# PAGE05_88-QFN-DEVICE_CO.net
KiCad netlist of a schematic drawn in Altium Designer
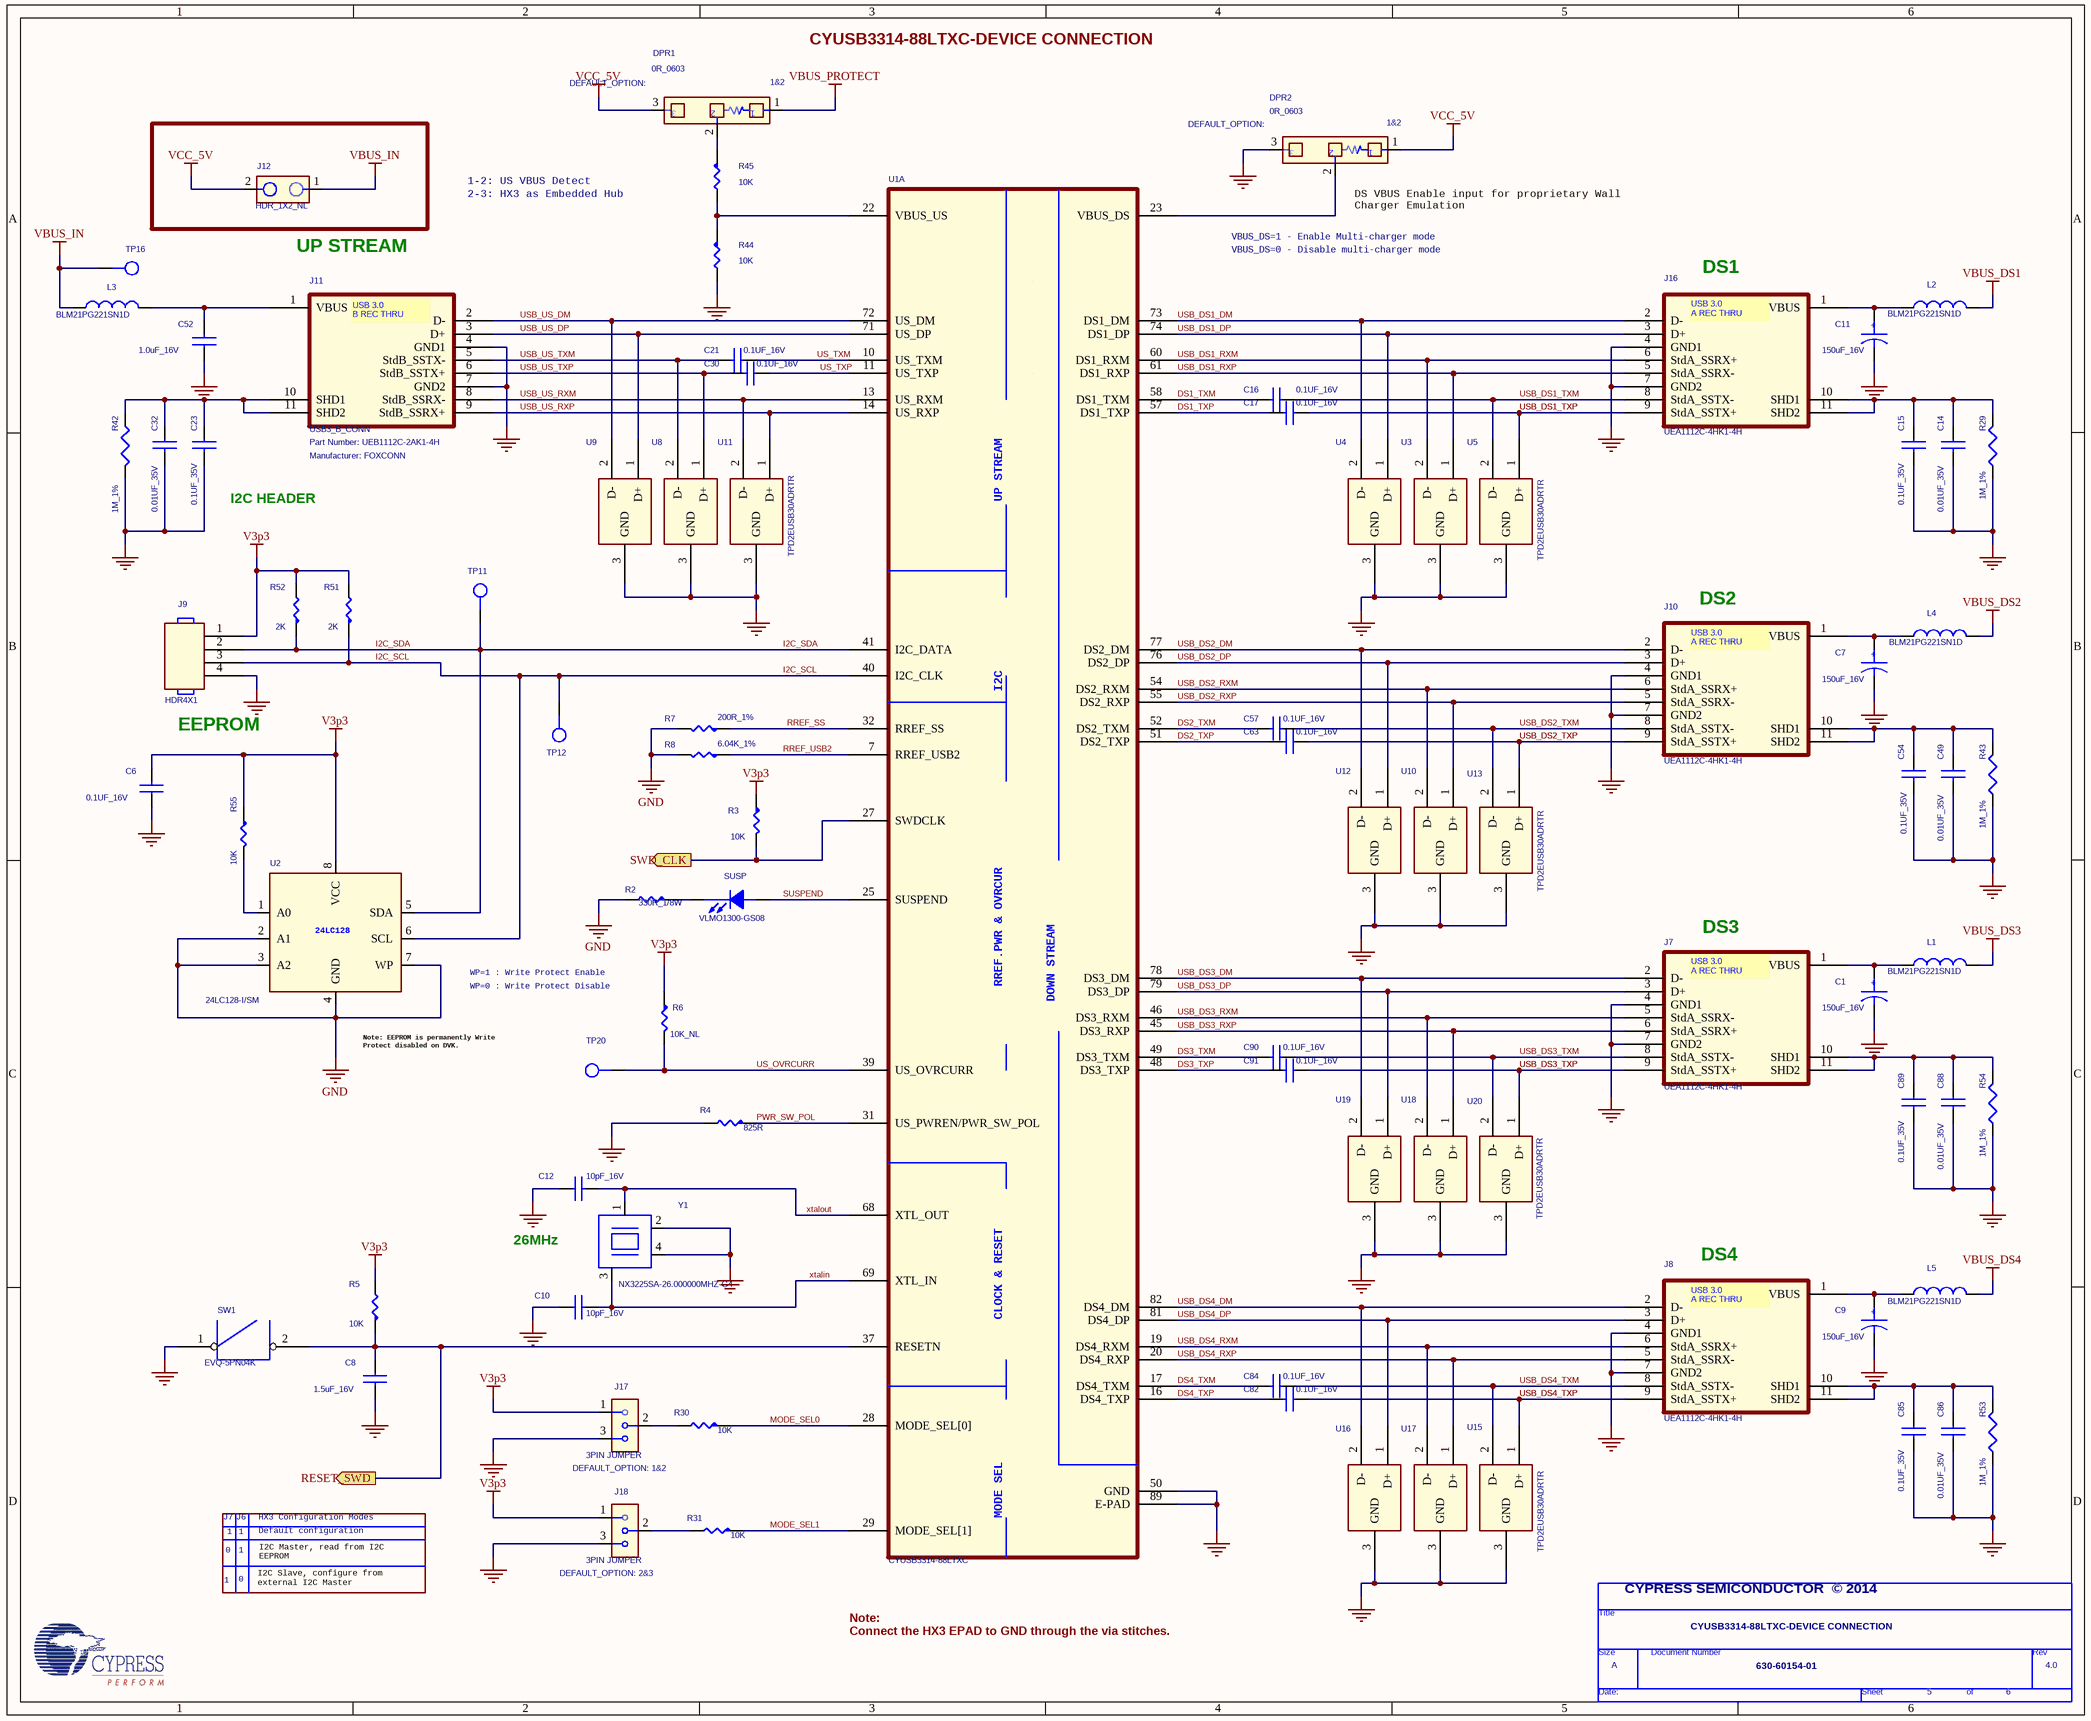
[diagram p0: PAGE05_88-QFN-DEVICE CO.SchDoc]

(export (version "E")
  (design (tool "Eeschema 10.0.6"))
  (components
    (comp (ref "*")
      (value "TitleBlock0")
      (fields
        (field (name "PAGE COUNT") "6")
        (field (name "PAGE NUMBER") "5")
        (field (name "PAGE SIZE") "A")
        (field (name "TITLE") "CYUSB3314-88LTXC-DEVICE CONNECTION")
        (field (name "REVCODE") "4.0")
        (field (name "DOC") "630-60154-01")
      )
      (libsource (lib "*") (part "TitleBlock0"))
    )
    (comp (ref "C1")
      (value "150uF_16V")
      (description "CAP ALUM 150UF 16V 20% SMD")
      (fields
        (field (name "PART NUMBER") "EEE-FK1C151XP")
        (field (name "MANUFACTURER") "Panasonic Electronic Components")
      )
      (libsource (lib "*") (part "CAP POL"))
    )
    (comp (ref "C6")
      (value "0.1UF_16V")
      (footprint "CAPC1005X56M")
      (libsource (lib "*") (part "CAPACITOR NON-POL"))
    )
    (comp (ref "C7")
      (value "150uF_16V")
      (description "CAP ALUM 150UF 16V 20% SMD")
      (fields
        (field (name "PART NUMBER") "EEE-FK1C151XP")
        (field (name "MANUFACTURER") "Panasonic Electronic Components")
      )
      (libsource (lib "*") (part "CAP POL"))
    )
    (comp (ref "C8")
      (value "1.5uF_16V")
      (footprint "CAPC1608X90M")
      (description "CAP CER 1.5UF 10V 10% X7R 0805")
      (fields (field (name "MANUFACTURER") "TDK Corporation"))
      (libsource (lib "*") (part "CAPACITOR NON-POL"))
    )
    (comp (ref "C9")
      (value "150uF_16V")
      (description "CAP ALUM 150UF 16V 20% SMD")
      (fields
        (field (name "PART NUMBER") "EEE-FK1C151XP")
        (field (name "MANUFACTURER") "Panasonic Electronic Components")
      )
      (libsource (lib "*") (part "CAP POL"))
    )
    (comp (ref "C10")
      (value "10pF_16V")
      (footprint "CAPC1608X90M")
      (libsource (lib "*") (part "CAPACITOR NON-POL"))
    )
    (comp (ref "C11")
      (value "150uF_16V")
      (description "CAP ALUM 150UF 16V 20% SMD")
      (fields
        (field (name "PART NUMBER") "EEE-FK1C151XP")
        (field (name "MANUFACTURER") "Panasonic Electronic Components")
      )
      (libsource (lib "*") (part "CAP POL"))
    )
    (comp (ref "C12")
      (value "10pF_16V")
      (footprint "CAPC1608X90M")
      (libsource (lib "*") (part "CAPACITOR NON-POL"))
    )
    (comp (ref "C14")
      (value "0.01UF_35V")
      (fields (field (name "PART NUMBER") "C1005X7R1V103M050BB"))
      (libsource (lib "*") (part "CAPACITOR NON-POL"))
    )
    (comp (ref "C15")
      (value "0.1UF_35V")
      (fields (field (name "PART NUMBER") "C1005X7R1V104K050BB"))
      (libsource (lib "*") (part "CAPACITOR NON-POL"))
    )
    (comp (ref "C16")
      (value "0.1UF_16V")
      (footprint "CAPC1005X56M")
      (libsource (lib "*") (part "CAPACITOR NON-POL"))
    )
    (comp (ref "C17")
      (value "0.1UF_16V")
      (footprint "CAPC1005X56M")
      (libsource (lib "*") (part "CAPACITOR NON-POL"))
    )
    (comp (ref "C21")
      (value "0.1UF_16V")
      (footprint "CAPC1005X56M")
      (libsource (lib "*") (part "CAPACITOR NON-POL"))
    )
    (comp (ref "C23")
      (value "0.1UF_35V")
      (fields (field (name "PART NUMBER") "C1005X7R1V104K050BB"))
      (libsource (lib "*") (part "CAPACITOR NON-POL"))
    )
    (comp (ref "C30")
      (value "0.1UF_16V")
      (footprint "CAPC1005X56M")
      (libsource (lib "*") (part "CAPACITOR NON-POL"))
    )
    (comp (ref "C32")
      (value "0.01UF_35V")
      (fields (field (name "PART NUMBER") "C1005X7R1V103M050BB"))
      (libsource (lib "*") (part "CAPACITOR NON-POL"))
    )
    (comp (ref "C49")
      (value "0.01UF_35V")
      (fields (field (name "PART NUMBER") "C1005X7R1V103M050BB"))
      (libsource (lib "*") (part "CAPACITOR NON-POL"))
    )
    (comp (ref "C52")
      (value "1.0uF_16V")
      (footprint "CAPC1005X56M")
      (libsource (lib "*") (part "CAPACITOR NON-POL"))
    )
    (comp (ref "C54")
      (value "0.1UF_35V")
      (fields (field (name "PART NUMBER") "C1005X7R1V104K050BB"))
      (libsource (lib "*") (part "CAPACITOR NON-POL"))
    )
    (comp (ref "C57")
      (value "0.1UF_16V")
      (footprint "CAPC1005X56M")
      (libsource (lib "*") (part "CAPACITOR NON-POL"))
    )
    (comp (ref "C63")
      (value "0.1UF_16V")
      (footprint "CAPC1005X56M")
      (libsource (lib "*") (part "CAPACITOR NON-POL"))
    )
    (comp (ref "C82")
      (value "0.1UF_16V")
      (footprint "CAPC1005X56M")
      (libsource (lib "*") (part "CAPACITOR NON-POL"))
    )
    (comp (ref "C84")
      (value "0.1UF_16V")
      (footprint "CAPC1005X56M")
      (libsource (lib "*") (part "CAPACITOR NON-POL"))
    )
    (comp (ref "C85")
      (value "0.1UF_35V")
      (fields (field (name "PART NUMBER") "C1005X7R1V104K050BB"))
      (libsource (lib "*") (part "CAPACITOR NON-POL"))
    )
    (comp (ref "C86")
      (value "0.01UF_35V")
      (fields (field (name "PART NUMBER") "C1005X7R1V103M050BB"))
      (libsource (lib "*") (part "CAPACITOR NON-POL"))
    )
    (comp (ref "C88")
      (value "0.01UF_35V")
      (fields (field (name "PART NUMBER") "C1005X7R1V103M050BB"))
      (libsource (lib "*") (part "CAPACITOR NON-POL"))
    )
    (comp (ref "C89")
      (value "0.1UF_35V")
      (fields (field (name "PART NUMBER") "C1005X7R1V104K050BB"))
      (libsource (lib "*") (part "CAPACITOR NON-POL"))
    )
    (comp (ref "C90")
      (value "0.1UF_16V")
      (footprint "CAPC1005X56M")
      (libsource (lib "*") (part "CAPACITOR NON-POL"))
    )
    (comp (ref "C91")
      (value "0.1UF_16V")
      (footprint "CAPC1005X56M")
      (libsource (lib "*") (part "CAPACITOR NON-POL"))
    )
    (comp (ref "DPR1")
      (value "0R_0603")
      (description "Resistor, 4.7K, 0402, 1/10W, 5%")
      (fields (field (name "MOUNTING STATUS") "1&2") (field (name "PART NUMBER") "ERJ-2GEJ472X"))
      (libsource (lib "*") (part "DPR12_0"))
    )
    (comp (ref "DPR2")
      (value "0R_0603")
      (description "Resistor, 4.7K, 0402, 1/10W, 5%")
      (fields (field (name "MOUNTING STATUS") "1&2") (field (name "PART NUMBER") "ERJ-2GEJ472X"))
      (libsource (lib "*") (part "DPR12_0"))
    )
    (comp (ref "J7")
      (value "UEA1112C-4HK1-4H")
      (description "9 Position Right Angle 3.0 USB Connector")
      (fields (field (name "MANUFACTURER") "FOXCONN"))
      (libsource (lib "*") (part "UEA1112C-4HK1-4H"))
    )
    (comp (ref "J8")
      (value "UEA1112C-4HK1-4H")
      (description "9 Position Right Angle 3.0 USB Connector")
      (fields (field (name "MANUFACTURER") "FOXCONN"))
      (libsource (lib "*") (part "UEA1112C_TX"))
    )
    (comp (ref "J9")
      (value "HDR4X1")
      (description "CONN HEADER 4POS .100\" SNGL GOLD")
      (fields (field (name "MANUFACTURER") "Samtec Inc") (field (name "PART NUMBER") "TSW-104-08-G-S"))
      (libsource (lib "*") (part "HEADER 4"))
    )
    (comp (ref "J10")
      (value "UEA1112C-4HK1-4H")
      (description "9 Position Right Angle 3.0 USB Connector")
      (fields (field (name "MANUFACTURER") "FOXCONN"))
      (libsource (lib "*") (part "UEA1112C_TX"))
    )
    (comp (ref "J11")
      (value "USB3_B_CONN")
      (footprint "FOXCONN_UEB1112C-2AK1-4H")
      (description "USB 3.0 B Series Right Angle,T/H 9 Pos")
      (fields (field (name "MANUFACTURER") "FOXCONN") (field (name "PART NUMBER") "UEB1112C-2AK1-4H"))
      (libsource (lib "*") (part "UEB1112C-2AK1-4H"))
    )
    (comp (ref "J12")
      (value "HDR_1X2_NL")
      (footprint "SAMTEC_TSW-102-08-G-S")
      (fields (field (name "MANUFACTURER") "Samtec Inc") (field (name "PART NUMBER") "TSW-102-08-G-S"))
      (libsource (lib "*") (part "HEADER_1x2"))
    )
    (comp (ref "J16")
      (value "UEA1112C-4HK1-4H")
      (description "9 Position Right Angle 3.0 USB Connector")
      (fields (field (name "MANUFACTURER") "FOXCONN"))
      (libsource (lib "*") (part "UEA1112C_TX"))
    )
    (comp (ref "J17")
      (value "3PIN JUMPER")
      (description "CONN HEADER VERT 3POS .100 TIN")
      (fields
        (field (name "PART NUMBER") "3-644456-3")
        (field (name "MANUFACTURER") "Tyco Electronics")
        (field (name "DEFAULT_OPTION") "1&2")
      )
      (libsource (lib "*") (part "3PIN JUM"))
    )
    (comp (ref "J18")
      (value "3PIN JUMPER")
      (description "CONN HEADER VERT 3POS .100 TIN")
      (fields
        (field (name "PART NUMBER") "3-644456-3")
        (field (name "MANUFACTURER") "Tyco Electronics")
        (field (name "DEFAULT_OPTION") "2&3")
      )
      (libsource (lib "*") (part "3PIN JUM"))
    )
    (comp (ref "L1")
      (value "BLM21PG221SN1D")
      (description "FERRITE CHIP 220 OHM 2A 0805")
      (fields (field (name "MANUFACTURER") "Murata"))
      (libsource (lib "*") (part "INDUCTOR"))
    )
    (comp (ref "L2")
      (value "BLM21PG221SN1D")
      (description "FERRITE CHIP 220 OHM 2A 0805")
      (fields (field (name "MANUFACTURER") "Murata"))
      (libsource (lib "*") (part "INDUCTOR"))
    )
    (comp (ref "L3")
      (value "BLM21PG221SN1D")
      (description "FERRITE CHIP 220 OHM 2A 0805")
      (fields (field (name "MANUFACTURER") "Murata"))
      (libsource (lib "") (part "INDUCTOR_1"))
    )
    (comp (ref "L4")
      (value "BLM21PG221SN1D")
      (description "FERRITE CHIP 220 OHM 2A 0805")
      (fields (field (name "MANUFACTURER") "Murata"))
      (libsource (lib "*") (part "INDUCTOR"))
    )
    (comp (ref "L5")
      (value "BLM21PG221SN1D")
      (description "FERRITE CHIP 220 OHM 2A 0805")
      (fields (field (name "MANUFACTURER") "Murata"))
      (libsource (lib "*") (part "INDUCTOR"))
    )
    (comp (ref "R2") (value "330R_1/8W") (footprint "RESC1608X50M") (libsource (lib "*") (part "R_Dup1")))
    (comp (ref "R3")
      (value "10K")
      (footprint "RESC1005X40M")
      (description "RES 10.0K OHM 1/10W 1% 0603 SMD")
      (fields (field (name "MANUFACTURER") "Panasonic - ECG") (field (name "PART NUMBER") "ERJ-3EKF1002V"))
      (libsource (lib "*") (part "R_Dup1"))
    )
    (comp (ref "R4")
      (value "825R")
      (footprint "RESC1005X40M")
      (fields (field (name "MANUFACTURER") "Panasonic") (field (name "PART NUMBER") "ERJ-2RKF49.9X"))
      (libsource (lib "*") (part "R_Dup1"))
    )
    (comp (ref "R5")
      (value "10K")
      (footprint "RESC1608X55M")
      (fields (field (name "PART NUMBER") "ERJ-2RKF49.9X") (field (name "MANUFACTURER") "Panasonic"))
      (libsource (lib "*") (part "R_Dup1"))
    )
    (comp (ref "R6")
      (value "10K_NL")
      (footprint "RESC1005X40M")
      (description "RES 10.0K OHM 1/10W 1% 0603 SMD")
      (fields (field (name "PART NUMBER") "ERJ-3EKF1002V") (field (name "MANUFACTURER") "Panasonic - ECG"))
      (libsource (lib "*") (part "R_Dup1"))
    )
    (comp (ref "R7")
      (value "200R_1%")
      (footprint "RESC1608X50M")
      (description "RES 200 OHM 1% 0603 SMD")
      (fields (field (name "MANUFACTURER") "Stackpole") (field (name "PART NUMBER") "RNCP0603FTD200R"))
      (libsource (lib "*") (part "R_Dup1"))
    )
    (comp (ref "R8")
      (value "6.04K_1%")
      (footprint "RESC1608X55M_A")
      (description "RES 6.04K OHM .25W 1% 0603 SMD")
      (fields (field (name "PART NUMBER") "CRCW06036K04FKEAHP") (field (name "MANUFACTURER") "Vishay Dale"))
      (libsource (lib "*") (part "R_Dup1"))
    )
    (comp (ref "R29")
      (value "1M_1%")
      (description "RES 1M OHM 1/10W 1% 0603 SMD")
      (fields (field (name "PART NUMBER") "ERJ-3EKF1004V"))
      (libsource (lib "*") (part "R"))
    )
    (comp (ref "R30")
      (value "10K")
      (footprint "RESC1005X40M")
      (fields (field (name "MANUFACTURER") "Panasonic") (field (name "PART NUMBER") "ERJ-2RKF49.9X"))
      (libsource (lib "*") (part "R_Dup1"))
    )
    (comp (ref "R31")
      (value "10K")
      (footprint "RESC1005X40M")
      (fields (field (name "MANUFACTURER") "Panasonic") (field (name "PART NUMBER") "ERJ-2RKF49.9X"))
      (libsource (lib "*") (part "R_Dup1"))
    )
    (comp (ref "R42")
      (value "1M_1%")
      (description "RES 1M OHM 1/10W 1% 0603 SMD")
      (fields (field (name "PART NUMBER") "ERJ-3EKF1004V") (field (name "MANUFACTURER") "Panasonic"))
      (libsource (lib "*") (part "R"))
    )
    (comp (ref "R43")
      (value "1M_1%")
      (description "RES 1M OHM 1/10W 1% 0603 SMD")
      (fields (field (name "MANUFACTURER") "Panasonic") (field (name "PART_NUMBER") "ERJ-3EKF1004V"))
      (libsource (lib "*") (part "R"))
    )
    (comp (ref "R44")
      (value "10K")
      (footprint "RESC1005X40M")
      (fields (field (name "PART NUMBER") "ERJ-2RKF4990X") (field (name "MANUFACTURER") "Panasonic"))
      (libsource (lib "*") (part "R_Dup1"))
    )
    (comp (ref "R45")
      (value "10K")
      (footprint "RESC1005X40M")
      (fields (field (name "MANUFACTURER") "Panasonic") (field (name "PART NUMBER") "ERJ-2GE0R00X"))
      (libsource (lib "*") (part "R_Dup1"))
    )
    (comp (ref "R51")
      (value "2K")
      (footprint "RESC1608X55M")
      (description "RES 2.00K OHM 1/10W 1% 0603 SMD")
      (fields
        (field (name "PART NUMBER") "MCR03EZPFX2001")
        (field (name "MANUFACTURER") "Rohm Semiconductor")
      )
      (libsource (lib "*") (part "R_Dup1"))
    )
    (comp (ref "R52")
      (value "2K")
      (footprint "RESC1608X55M")
      (description "RES 2.00K OHM 1/10W 1% 0603 SMD")
      (fields
        (field (name "MANUFACTURER") "Rohm Semiconductor")
        (field (name "PART NUMBER") "MCR03EZPFX2001")
      )
      (libsource (lib "*") (part "R_Dup1"))
    )
    (comp (ref "R53")
      (value "1M_1%")
      (description "RES 1M OHM 1/10W 1% 0603 SMD")
      (fields (field (name "MANUFACTURER") "Panasonic") (field (name "PART NUMBER") "ERJ-3EKF1004V"))
      (libsource (lib "*") (part "R"))
    )
    (comp (ref "R54")
      (value "1M_1%")
      (description "RES 1M OHM 1/10W 1% 0603 SMD")
      (fields (field (name "MANUFACTURER") "Panasonic") (field (name "PART NUMBER") "ERJ-3EKF1004V"))
      (libsource (lib "*") (part "R"))
    )
    (comp (ref "R55")
      (value "10K")
      (footprint "RESC1608X55M")
      (description "RES 10.0K OHM 1/10W 1% 0603 SMD")
      (fields (field (name "PART NUMBER") "ERJ-3EKF1002V") (field (name "MANUFACTURER") "Panasonic - ECG"))
      (libsource (lib "*") (part "R_Dup1"))
    )
    (comp (ref "SUSP") (value "VLMO1300-GS08") (libsource (lib "*") (part "LED")))
    (comp (ref "SW1") (value "EVQ-5PN04K") (libsource (lib "*") (part "B3U1000P")))
    (comp (ref "TP11")
      (value "TP_YEL")
      (footprint "KEYSTONE_5000")
      (description "TEST POINT PC MINI .040\"D RED")
      (fields (field (name "PART_NUMBER") "5000") (field (name "MANUFACTURER") "Keystone"))
      (libsource (lib "*") (part "TP"))
    )
    (comp (ref "TP12")
      (value "TP_YEL")
      (footprint "KEYSTONE_5000")
      (description "TEST POINT PC MINI .040\"D RED")
      (fields (field (name "PART NUMBER") "5000") (field (name "MANUFACTURER") "Keystone"))
      (libsource (lib "*") (part "TP"))
    )
    (comp (ref "TP16")
      (value "TP_RED")
      (footprint "KEYSTONE_5000")
      (description "TEST POINT PC MINI .040\"D RED")
      (fields (field (name "PART NUMBER") "5000") (field (name "MANUFACTURER") "Keystone"))
      (libsource (lib "*") (part "TP"))
    )
    (comp (ref "TP20")
      (value "TP_YEL")
      (footprint "KEYSTONE_5000")
      (description "TEST POINT PC MINI .040\"D RED")
      (fields (field (name "PART_NUMBER") "5000") (field (name "MANUFACTURER") "Keystone"))
      (libsource (lib "*") (part "TP"))
    )
    (comp (ref "U1")
      (value "CYUSB3314-88LTXC")
      (footprint "QFN40P1000X1000X100-89M")
      (libsource (lib "*") (part "CYUSB3314-88LTXC_2"))
    )
    (comp (ref "U2")
      (value "24LC128-I/SM")
      (footprint "SOIC127P790X203-8M")
      (description "IC EEPROM 128KBIT 400KHZ 8SOIC")
      (fields (field (name "MANUFACTURER") "Microchip Technology"))
      (libsource (lib "*") (part "24LC128"))
    )
    (comp (ref "U3")
      (value "TPD2EUSB30ADRTR")
      (footprint "SOTFL35P100X50-3M")
      (libsource (lib "*") (part "TPD2EUSB30ADRTR"))
    )
    (comp (ref "U4")
      (value "TPD2EUSB30ADRTR")
      (footprint "SOTFL35P100X50-3M")
      (libsource (lib "*") (part "TPD2EUSB30ADRTR"))
    )
    (comp (ref "U5")
      (value "TPD2EUSB30ADRTR")
      (footprint "SOTFL35P100X50-3M")
      (libsource (lib "*") (part "TPD2EUSB30ADRTR"))
    )
    (comp (ref "U8")
      (value "TPD2EUSB30ADRTR")
      (footprint "SOTFL35P100X50-3M")
      (libsource (lib "*") (part "TPD2EUSB30ADRTR"))
    )
    (comp (ref "U9")
      (value "TPD2EUSB30ADRTR")
      (footprint "SOTFL35P100X50-3M")
      (libsource (lib "*") (part "TPD2EUSB30ADRTR"))
    )
    (comp (ref "U10")
      (value "TPD2EUSB30ADRTR")
      (footprint "SOTFL35P100X50-3M")
      (libsource (lib "*") (part "TPD2EUSB30ADRTR"))
    )
    (comp (ref "U11")
      (value "TPD2EUSB30ADRTR")
      (footprint "SOTFL35P100X50-3M")
      (libsource (lib "*") (part "TPD2EUSB30ADRTR"))
    )
    (comp (ref "U12")
      (value "TPD2EUSB30ADRTR")
      (footprint "SOTFL35P100X50-3M")
      (libsource (lib "*") (part "TPD2EUSB30ADRTR"))
    )
    (comp (ref "U13")
      (value "TPD2EUSB30ADRTR")
      (footprint "SOTFL35P100X50-3M")
      (libsource (lib "*") (part "TPD2EUSB30ADRTR"))
    )
    (comp (ref "U15")
      (value "TPD2EUSB30ADRTR")
      (footprint "SOTFL35P100X50-3M")
      (libsource (lib "*") (part "TPD2EUSB30ADRTR"))
    )
    (comp (ref "U16")
      (value "TPD2EUSB30ADRTR")
      (footprint "SOTFL35P100X50-3M")
      (libsource (lib "*") (part "TPD2EUSB30ADRTR"))
    )
    (comp (ref "U17")
      (value "TPD2EUSB30ADRTR")
      (footprint "SOTFL35P100X50-3M")
      (libsource (lib "*") (part "TPD2EUSB30ADRTR"))
    )
    (comp (ref "U18")
      (value "TPD2EUSB30ADRTR")
      (footprint "SOTFL35P100X50-3M")
      (libsource (lib "*") (part "TPD2EUSB30ADRTR"))
    )
    (comp (ref "U19")
      (value "TPD2EUSB30ADRTR")
      (footprint "SOTFL35P100X50-3M")
      (libsource (lib "*") (part "TPD2EUSB30ADRTR"))
    )
    (comp (ref "U20")
      (value "TPD2EUSB30ADRTR")
      (footprint "SOTFL35P100X50-3M")
      (libsource (lib "*") (part "TPD2EUSB30ADRTR"))
    )
    (comp (ref "Y1")
      (value "NX3225SA-26.000000MHZ-G4")
      (fields (field (name "MANUFACTURER") "NDK"))
      (libsource (lib "*") (part "CRYSTAL_1"))
    )
  )
  (nets
    (net (code "1") (name "/DS1_TXM") (class "Default")
      (node (ref "C16") (pin "2") (pinfunction "2_2") (pintype "passive"))
      (node (ref "U1") (pin "58") (pinfunction "DS1_TXM_58") (pintype "passive"))
    )
    (net (code "2") (name "/DS1_TXP") (class "Default")
      (node (ref "C17") (pin "2") (pinfunction "2_2") (pintype "passive"))
      (node (ref "U1") (pin "57") (pinfunction "DS1_TXP_57") (pintype "passive"))
    )
    (net (code "3") (name "/DS2_TXM") (class "Default")
      (node (ref "C57") (pin "2") (pinfunction "2_2") (pintype "passive"))
      (node (ref "U1") (pin "52") (pinfunction "DS2_TXM_52") (pintype "passive"))
    )
    (net (code "4") (name "/DS2_TXP") (class "Default")
      (node (ref "C63") (pin "2") (pinfunction "2_2") (pintype "passive"))
      (node (ref "U1") (pin "51") (pinfunction "DS2_TXP_51") (pintype "passive"))
    )
    (net (code "5") (name "/DS3_TXM") (class "Default")
      (node (ref "C90") (pin "2") (pinfunction "2_2") (pintype "passive"))
      (node (ref "U1") (pin "49") (pinfunction "DS3_TXM_49") (pintype "passive"))
    )
    (net (code "6") (name "/DS3_TXP") (class "Default")
      (node (ref "C91") (pin "2") (pinfunction "2_2") (pintype "passive"))
      (node (ref "U1") (pin "48") (pinfunction "DS3_TXP_48") (pintype "passive"))
    )
    (net (code "7") (name "/DS4_TXM") (class "Default")
      (node (ref "C84") (pin "2") (pinfunction "2_2") (pintype "passive"))
      (node (ref "U1") (pin "17") (pinfunction "DS4_TXM_17") (pintype "passive"))
    )
    (net (code "8") (name "/DS4_TXP") (class "Default")
      (node (ref "C82") (pin "2") (pinfunction "2_2") (pintype "passive"))
      (node (ref "U1") (pin "16") (pinfunction "DS4_TXP_16") (pintype "passive"))
    )
    (net (code "9") (name "/I2C_SCL") (class "Default")
      (node (ref "J9") (pin "3") (pinfunction "3_3") (pintype "passive"))
      (node (ref "R51") (pin "1") (pinfunction "1_1") (pintype "passive"))
      (node (ref "TP12") (pin "1") (pinfunction "TP_1") (pintype "passive"))
      (node (ref "U1") (pin "40") (pinfunction "I2C_CLK_40") (pintype "passive"))
      (node (ref "U2") (pin "6") (pinfunction "SCL_6") (pintype "passive"))
    )
    (net (code "10") (name "/I2C_SDA") (class "Default")
      (node (ref "J9") (pin "2") (pinfunction "2_2") (pintype "passive"))
      (node (ref "R52") (pin "1") (pinfunction "1_1") (pintype "passive"))
      (node (ref "TP11") (pin "1") (pinfunction "TP_1") (pintype "passive"))
      (node (ref "U1") (pin "41") (pinfunction "I2C_DATA_41") (pintype "passive"))
      (node (ref "U2") (pin "5") (pinfunction "SDA_5") (pintype "passive"))
    )
    (net (code "11") (name "/MODE_SEL0") (class "Default")
      (node (ref "R30") (pin "1") (pinfunction "1_1") (pintype "passive"))
      (node (ref "U1") (pin "28") (pinfunction "MODE_SEL[0]_28") (pintype "passive"))
    )
    (net (code "12") (name "/MODE_SEL1") (class "Default")
      (node (ref "R31") (pin "1") (pinfunction "1_1") (pintype "passive"))
      (node (ref "U1") (pin "29") (pinfunction "MODE_SEL[1]_29") (pintype "passive"))
    )
    (net (code "13") (name "/PWR_SW_POL") (class "Default")
      (node (ref "R4") (pin "1") (pinfunction "1_1") (pintype "passive"))
      (node (ref "U1") (pin "31") (pinfunction "US_PWREN/PWR_SW_POL_31") (pintype "passive"))
    )
    (net (code "14") (name "/RESET_SWD") (class "Default")
      (node (ref "C8") (pin "1") (pinfunction "1_1") (pintype "passive"))
      (node (ref "R5") (pin "1") (pinfunction "1_1") (pintype "passive"))
      (node (ref "SW1") (pin "2") (pinfunction "2_2") (pintype "passive"))
      (node (ref "U1") (pin "37") (pinfunction "RESETN_37") (pintype "passive"))
    )
    (net (code "15") (name "/RREF_SS") (class "Default")
      (node (ref "R7") (pin "1") (pinfunction "1_1") (pintype "passive"))
      (node (ref "U1") (pin "32") (pinfunction "RREF_SS_32") (pintype "passive"))
    )
    (net (code "16") (name "/RREF_USB2") (class "Default")
      (node (ref "R8") (pin "1") (pinfunction "1_1") (pintype "passive"))
      (node (ref "U1") (pin "7") (pinfunction "RREF_USB2_7") (pintype "passive"))
    )
    (net (code "17") (name "/SUSPEND") (class "Default")
      (node (ref "SUSP") (pin "1") (pinfunction "ANODE_1") (pintype "passive"))
      (node (ref "U1") (pin "25") (pinfunction "SUSPEND_25") (pintype "passive"))
    )
    (net (code "18") (name "/SWD_CLK") (class "Default")
      (node (ref "R3") (pin "2") (pinfunction "2_2") (pintype "passive"))
      (node (ref "U1") (pin "27") (pinfunction "SWDCLK_27") (pintype "passive"))
    )
    (net (code "19") (name "/USB_DS1_DM") (class "Default")
      (node (ref "J16") (pin "2") (pinfunction "D-_2") (pintype "passive"))
      (node (ref "U1") (pin "73") (pinfunction "DS1_DM_73") (pintype "passive"))
      (node (ref "U4") (pin "2") (pinfunction "D-_2") (pintype "passive"))
    )
    (net (code "20") (name "/USB_DS1_DP") (class "Default")
      (node (ref "J16") (pin "3") (pinfunction "D+_3") (pintype "passive"))
      (node (ref "U1") (pin "74") (pinfunction "DS1_DP_74") (pintype "passive"))
      (node (ref "U4") (pin "1") (pinfunction "D+_1") (pintype "passive"))
    )
    (net (code "21") (name "/USB_DS1_RXM") (class "Default")
      (node (ref "J16") (pin "6") (pinfunction "StdA_SSRX+_6") (pintype "passive"))
      (node (ref "U1") (pin "60") (pinfunction "DS1_RXM_60") (pintype "passive"))
      (node (ref "U3") (pin "2") (pinfunction "D-_2") (pintype "passive"))
    )
    (net (code "22") (name "/USB_DS1_RXP") (class "Default")
      (node (ref "J16") (pin "5") (pinfunction "StdA_SSRX-_5") (pintype "passive"))
      (node (ref "U1") (pin "61") (pinfunction "DS1_RXP_61") (pintype "passive"))
      (node (ref "U3") (pin "1") (pinfunction "D+_1") (pintype "passive"))
    )
    (net (code "23") (name "/USB_DS1_TXM") (class "Default")
      (node (ref "C16") (pin "1") (pinfunction "1_1") (pintype "passive"))
      (node (ref "J16") (pin "8") (pinfunction "StdA_SSTX-_8") (pintype "passive"))
      (node (ref "U5") (pin "2") (pinfunction "D-_2") (pintype "passive"))
    )
    (net (code "24") (name "/USB_DS1_TXP") (class "Default")
      (node (ref "C17") (pin "1") (pinfunction "1_1") (pintype "passive"))
      (node (ref "J16") (pin "9") (pinfunction "StdA_SSTX+_9") (pintype "passive"))
      (node (ref "U5") (pin "1") (pinfunction "D+_1") (pintype "passive"))
    )
    (net (code "25") (name "/USB_DS2_DM") (class "Default")
      (node (ref "J10") (pin "2") (pinfunction "D-_2") (pintype "passive"))
      (node (ref "U1") (pin "77") (pinfunction "DS2_DM_77") (pintype "passive"))
      (node (ref "U12") (pin "2") (pinfunction "D-_2") (pintype "passive"))
    )
    (net (code "26") (name "/USB_DS2_DP") (class "Default")
      (node (ref "J10") (pin "3") (pinfunction "D+_3") (pintype "passive"))
      (node (ref "U1") (pin "76") (pinfunction "DS2_DP_76") (pintype "passive"))
      (node (ref "U12") (pin "1") (pinfunction "D+_1") (pintype "passive"))
    )
    (net (code "27") (name "/USB_DS2_RXM") (class "Default")
      (node (ref "J10") (pin "6") (pinfunction "StdA_SSRX+_6") (pintype "passive"))
      (node (ref "U1") (pin "54") (pinfunction "DS2_RXM_54") (pintype "passive"))
      (node (ref "U10") (pin "2") (pinfunction "D-_2") (pintype "passive"))
    )
    (net (code "28") (name "/USB_DS2_RXP") (class "Default")
      (node (ref "J10") (pin "5") (pinfunction "StdA_SSRX-_5") (pintype "passive"))
      (node (ref "U1") (pin "55") (pinfunction "DS2_RXP_55") (pintype "passive"))
      (node (ref "U10") (pin "1") (pinfunction "D+_1") (pintype "passive"))
    )
    (net (code "29") (name "/USB_DS2_TXM") (class "Default")
      (node (ref "C57") (pin "1") (pinfunction "1_1") (pintype "passive"))
      (node (ref "J10") (pin "8") (pinfunction "StdA_SSTX-_8") (pintype "passive"))
      (node (ref "U13") (pin "2") (pinfunction "D-_2") (pintype "passive"))
    )
    (net (code "30") (name "/USB_DS2_TXP") (class "Default")
      (node (ref "C63") (pin "1") (pinfunction "1_1") (pintype "passive"))
      (node (ref "J10") (pin "9") (pinfunction "StdA_SSTX+_9") (pintype "passive"))
      (node (ref "U13") (pin "1") (pinfunction "D+_1") (pintype "passive"))
    )
    (net (code "31") (name "/USB_DS3_DM") (class "Default")
      (node (ref "J7") (pin "2") (pinfunction "D-_2") (pintype "passive"))
      (node (ref "U1") (pin "78") (pinfunction "DS3_DM_78") (pintype "passive"))
      (node (ref "U19") (pin "2") (pinfunction "D-_2") (pintype "passive"))
    )
    (net (code "32") (name "/USB_DS3_DP") (class "Default")
      (node (ref "J7") (pin "3") (pinfunction "D+_3") (pintype "passive"))
      (node (ref "U1") (pin "79") (pinfunction "DS3_DP_79") (pintype "passive"))
      (node (ref "U19") (pin "1") (pinfunction "D+_1") (pintype "passive"))
    )
    (net (code "33") (name "/USB_DS3_RXM") (class "Default")
      (node (ref "J7") (pin "5") (pinfunction "StdA_SSRX-_5") (pintype "passive"))
      (node (ref "U1") (pin "46") (pinfunction "DS3_RXM_46") (pintype "passive"))
      (node (ref "U18") (pin "2") (pinfunction "D-_2") (pintype "passive"))
    )
    (net (code "34") (name "/USB_DS3_RXP") (class "Default")
      (node (ref "J7") (pin "6") (pinfunction "StdA_SSRX+_6") (pintype "passive"))
      (node (ref "U1") (pin "45") (pinfunction "DS3_RXP_45") (pintype "passive"))
      (node (ref "U18") (pin "1") (pinfunction "D+_1") (pintype "passive"))
    )
    (net (code "35") (name "/USB_DS3_TXM") (class "Default")
      (node (ref "C90") (pin "1") (pinfunction "1_1") (pintype "passive"))
      (node (ref "J7") (pin "8") (pinfunction "StdA_SSTX-_8") (pintype "passive"))
      (node (ref "U20") (pin "2") (pinfunction "D-_2") (pintype "passive"))
    )
    (net (code "36") (name "/USB_DS3_TXP") (class "Default")
      (node (ref "C91") (pin "1") (pinfunction "1_1") (pintype "passive"))
      (node (ref "J7") (pin "9") (pinfunction "StdA_SSTX+_9") (pintype "passive"))
      (node (ref "U20") (pin "1") (pinfunction "D+_1") (pintype "passive"))
    )
    (net (code "37") (name "/USB_DS4_DM") (class "Default")
      (node (ref "J8") (pin "2") (pinfunction "D-_2") (pintype "passive"))
      (node (ref "U1") (pin "82") (pinfunction "DS4_DM_82") (pintype "passive"))
      (node (ref "U16") (pin "2") (pinfunction "D-_2") (pintype "passive"))
    )
    (net (code "38") (name "/USB_DS4_DP") (class "Default")
      (node (ref "J8") (pin "3") (pinfunction "D+_3") (pintype "passive"))
      (node (ref "U1") (pin "81") (pinfunction "DS4_DP_81") (pintype "passive"))
      (node (ref "U16") (pin "1") (pinfunction "D+_1") (pintype "passive"))
    )
    (net (code "39") (name "/USB_DS4_RXM") (class "Default")
      (node (ref "J8") (pin "6") (pinfunction "StdA_SSRX+_6") (pintype "passive"))
      (node (ref "U1") (pin "19") (pinfunction "DS4_RXM_19") (pintype "passive"))
      (node (ref "U17") (pin "2") (pinfunction "D-_2") (pintype "passive"))
    )
    (net (code "40") (name "/USB_DS4_RXP") (class "Default")
      (node (ref "J8") (pin "5") (pinfunction "StdA_SSRX-_5") (pintype "passive"))
      (node (ref "U1") (pin "20") (pinfunction "DS4_RXP_20") (pintype "passive"))
      (node (ref "U17") (pin "1") (pinfunction "D+_1") (pintype "passive"))
    )
    (net (code "41") (name "/USB_DS4_TXM") (class "Default")
      (node (ref "C84") (pin "1") (pinfunction "1_1") (pintype "passive"))
      (node (ref "J8") (pin "8") (pinfunction "StdA_SSTX-_8") (pintype "passive"))
      (node (ref "U15") (pin "2") (pinfunction "D-_2") (pintype "passive"))
    )
    (net (code "42") (name "/USB_DS4_TXP") (class "Default")
      (node (ref "C82") (pin "1") (pinfunction "1_1") (pintype "passive"))
      (node (ref "J8") (pin "9") (pinfunction "StdA_SSTX+_9") (pintype "passive"))
      (node (ref "U15") (pin "1") (pinfunction "D+_1") (pintype "passive"))
    )
    (net (code "43") (name "/USB_US_DM") (class "Default")
      (node (ref "J11") (pin "2") (pinfunction "D-_2") (pintype "passive"))
      (node (ref "U1") (pin "72") (pinfunction "US_DM_72") (pintype "passive"))
      (node (ref "U9") (pin "2") (pinfunction "D-_2") (pintype "passive"))
    )
    (net (code "44") (name "/USB_US_DP") (class "Default")
      (node (ref "J11") (pin "3") (pinfunction "D+_3") (pintype "passive"))
      (node (ref "U1") (pin "71") (pinfunction "US_DP_71") (pintype "passive"))
      (node (ref "U9") (pin "1") (pinfunction "D+_1") (pintype "passive"))
    )
    (net (code "45") (name "/USB_US_RXM") (class "Default")
      (node (ref "J11") (pin "8") (pinfunction "StdB_SSRX-_8") (pintype "passive"))
      (node (ref "U1") (pin "13") (pinfunction "US_RXM_13") (pintype "passive"))
      (node (ref "U11") (pin "2") (pinfunction "D-_2") (pintype "passive"))
    )
    (net (code "46") (name "/USB_US_RXP") (class "Default")
      (node (ref "J11") (pin "9") (pinfunction "StdB_SSRX+_9") (pintype "passive"))
      (node (ref "U1") (pin "14") (pinfunction "US_RXP_14") (pintype "passive"))
      (node (ref "U11") (pin "1") (pinfunction "D+_1") (pintype "passive"))
    )
    (net (code "47") (name "/USB_US_TXM") (class "Default")
      (node (ref "C21") (pin "2") (pinfunction "2_2") (pintype "passive"))
      (node (ref "J11") (pin "5") (pinfunction "StdB_SSTX-_5") (pintype "passive"))
      (node (ref "U8") (pin "2") (pinfunction "D-_2") (pintype "passive"))
    )
    (net (code "48") (name "/USB_US_TXP") (class "Default")
      (node (ref "C30") (pin "2") (pinfunction "2_2") (pintype "passive"))
      (node (ref "J11") (pin "6") (pinfunction "StdB_SSTX+_6") (pintype "passive"))
      (node (ref "U8") (pin "1") (pinfunction "D+_1") (pintype "passive"))
    )
    (net (code "49") (name "/US_OVRCURR") (class "Default")
      (node (ref "R6") (pin "2") (pinfunction "2_2") (pintype "passive"))
      (node (ref "TP20") (pin "1") (pinfunction "TP_1") (pintype "passive"))
      (node (ref "U1") (pin "39") (pinfunction "US_OVRCURR_39") (pintype "passive"))
    )
    (net (code "50") (name "/US_TXM") (class "Default")
      (node (ref "C21") (pin "1") (pinfunction "1_1") (pintype "passive"))
      (node (ref "U1") (pin "10") (pinfunction "US_TXM_10") (pintype "passive"))
    )
    (net (code "51") (name "/US_TXP") (class "Default")
      (node (ref "C30") (pin "1") (pinfunction "1_1") (pintype "passive"))
      (node (ref "U1") (pin "11") (pinfunction "US_TXP_11") (pintype "passive"))
    )
    (net (code "52") (name "/xtalin") (class "Default")
      (node (ref "C10") (pin "2") (pinfunction "2_2") (pintype "passive"))
      (node (ref "U1") (pin "69") (pinfunction "XTL_IN_69") (pintype "passive"))
      (node (ref "Y1") (pin "3") (pinfunction "3_3") (pintype "passive"))
    )
    (net (code "53") (name "/xtalout") (class "Default")
      (node (ref "C12") (pin "2") (pinfunction "2_2") (pintype "passive"))
      (node (ref "U1") (pin "68") (pinfunction "XTL_OUT_68") (pintype "passive"))
      (node (ref "Y1") (pin "1") (pinfunction "1_1") (pintype "passive"))
    )
    (net (code "54") (name "GND") (class "Default")
      (node (ref "C1") (pin "2") (pinfunction "2_2") (pintype "passive"))
      (node (ref "C10") (pin "1") (pinfunction "1_1") (pintype "passive"))
      (node (ref "C11") (pin "2") (pinfunction "2_2") (pintype "passive"))
      (node (ref "C12") (pin "1") (pinfunction "1_1") (pintype "passive"))
      (node (ref "C14") (pin "2") (pinfunction "2_2") (pintype "passive"))
      (node (ref "C15") (pin "2") (pinfunction "2_2") (pintype "passive"))
      (node (ref "C23") (pin "2") (pinfunction "2_2") (pintype "passive"))
      (node (ref "C32") (pin "2") (pinfunction "2_2") (pintype "passive"))
      (node (ref "C49") (pin "2") (pinfunction "2_2") (pintype "passive"))
      (node (ref "C52") (pin "1") (pinfunction "1_1") (pintype "passive"))
      (node (ref "C54") (pin "2") (pinfunction "2_2") (pintype "passive"))
      (node (ref "C6") (pin "1") (pinfunction "1_1") (pintype "passive"))
      (node (ref "C7") (pin "2") (pinfunction "2_2") (pintype "passive"))
      (node (ref "C8") (pin "2") (pinfunction "2_2") (pintype "passive"))
      (node (ref "C85") (pin "2") (pinfunction "2_2") (pintype "passive"))
      (node (ref "C86") (pin "2") (pinfunction "2_2") (pintype "passive"))
      (node (ref "C88") (pin "2") (pinfunction "2_2") (pintype "passive"))
      (node (ref "C89") (pin "2") (pinfunction "2_2") (pintype "passive"))
      (node (ref "C9") (pin "2") (pinfunction "2_2") (pintype "passive"))
      (node (ref "DPR2") (pin "3") (pinfunction "3_3") (pintype "passive"))
      (node (ref "J10") (pin "4") (pinfunction "GND1_4") (pintype "passive"))
      (node (ref "J10") (pin "7") (pinfunction "GND2_7") (pintype "passive"))
      (node (ref "J11") (pin "4") (pinfunction "GND1_4") (pintype "passive"))
      (node (ref "J11") (pin "7") (pinfunction "GND2_7") (pintype "passive"))
      (node (ref "J16") (pin "4") (pinfunction "GND1_4") (pintype "passive"))
      (node (ref "J16") (pin "7") (pinfunction "GND2_7") (pintype "passive"))
      (node (ref "J17") (pin "3") (pinfunction "3_3") (pintype "passive"))
      (node (ref "J18") (pin "3") (pinfunction "3_3") (pintype "passive"))
      (node (ref "J7") (pin "4") (pinfunction "GND1_4") (pintype "passive"))
      (node (ref "J7") (pin "7") (pinfunction "GND2_7") (pintype "passive"))
      (node (ref "J8") (pin "4") (pinfunction "GND1_4") (pintype "passive"))
      (node (ref "J8") (pin "7") (pinfunction "GND2_7") (pintype "passive"))
      (node (ref "J9") (pin "4") (pinfunction "4_4") (pintype "passive"))
      (node (ref "R2") (pin "2") (pinfunction "2_2") (pintype "passive"))
      (node (ref "R29") (pin "2") (pinfunction "2_2") (pintype "passive"))
      (node (ref "R4") (pin "2") (pinfunction "2_2") (pintype "passive"))
      (node (ref "R42") (pin "2") (pinfunction "2_2") (pintype "passive"))
      (node (ref "R43") (pin "2") (pinfunction "2_2") (pintype "passive"))
      (node (ref "R44") (pin "2") (pinfunction "2_2") (pintype "passive"))
      (node (ref "R53") (pin "2") (pinfunction "2_2") (pintype "passive"))
      (node (ref "R54") (pin "2") (pinfunction "2_2") (pintype "passive"))
      (node (ref "R7") (pin "2") (pinfunction "2_2") (pintype "passive"))
      (node (ref "R8") (pin "2") (pinfunction "2_2") (pintype "passive"))
      (node (ref "SW1") (pin "1") (pinfunction "1_1") (pintype "passive"))
      (node (ref "U1") (pin "50") (pinfunction "GND_50") (pintype "passive"))
      (node (ref "U1") (pin "89") (pinfunction "E-PAD_89") (pintype "passive"))
      (node (ref "U10") (pin "3") (pinfunction "GND_3") (pintype "passive"))
      (node (ref "U11") (pin "3") (pinfunction "GND_3") (pintype "passive"))
      (node (ref "U12") (pin "3") (pinfunction "GND_3") (pintype "passive"))
      (node (ref "U13") (pin "3") (pinfunction "GND_3") (pintype "passive"))
      (node (ref "U15") (pin "3") (pinfunction "GND_3") (pintype "passive"))
      (node (ref "U16") (pin "3") (pinfunction "GND_3") (pintype "passive"))
      (node (ref "U17") (pin "3") (pinfunction "GND_3") (pintype "passive"))
      (node (ref "U18") (pin "3") (pinfunction "GND_3") (pintype "passive"))
      (node (ref "U19") (pin "3") (pinfunction "GND_3") (pintype "passive"))
      (node (ref "U2") (pin "2") (pinfunction "A1_2") (pintype "passive"))
      (node (ref "U2") (pin "3") (pinfunction "A2_3") (pintype "passive"))
      (node (ref "U2") (pin "4") (pinfunction "GND_4") (pintype "passive"))
      (node (ref "U2") (pin "7") (pinfunction "WP_7") (pintype "passive"))
      (node (ref "U20") (pin "3") (pinfunction "GND_3") (pintype "passive"))
      (node (ref "U3") (pin "3") (pinfunction "GND_3") (pintype "passive"))
      (node (ref "U4") (pin "3") (pinfunction "GND_3") (pintype "passive"))
      (node (ref "U5") (pin "3") (pinfunction "GND_3") (pintype "passive"))
      (node (ref "U8") (pin "3") (pinfunction "GND_3") (pintype "passive"))
      (node (ref "U9") (pin "3") (pinfunction "GND_3") (pintype "passive"))
      (node (ref "Y1") (pin "2") (pinfunction "2_2") (pintype "passive"))
      (node (ref "Y1") (pin "4") (pinfunction "4_4") (pintype "passive"))
    )
    (net (code "55") (name "Net-(DPR1-Pad2)") (class "Default")
      (node (ref "DPR1") (pin "2") (pinfunction "2_2") (pintype "passive"))
      (node (ref "R45") (pin "1") (pinfunction "1_1") (pintype "passive"))
    )
    (net (code "56") (name "Net-(J7-SHD1)") (class "Default")
      (node (ref "C88") (pin "1") (pinfunction "1_1") (pintype "passive"))
      (node (ref "C89") (pin "1") (pinfunction "1_1") (pintype "passive"))
      (node (ref "J7") (pin "10") (pinfunction "SHD1_10") (pintype "passive"))
      (node (ref "J7") (pin "11") (pinfunction "SHD2_11") (pintype "passive"))
      (node (ref "R54") (pin "1") (pinfunction "1_1") (pintype "passive"))
    )
    (net (code "57") (name "Net-(J7-VBUS)") (class "Default")
      (node (ref "C1") (pin "1") (pinfunction "1_1") (pintype "passive"))
      (node (ref "J7") (pin "1") (pinfunction "VBUS_1") (pintype "passive"))
      (node (ref "L1") (pin "2") (pinfunction "2_2") (pintype "passive"))
    )
    (net (code "58") (name "Net-(J8-SHD1)") (class "Default")
      (node (ref "C85") (pin "1") (pinfunction "1_1") (pintype "passive"))
      (node (ref "C86") (pin "1") (pinfunction "1_1") (pintype "passive"))
      (node (ref "J8") (pin "10") (pinfunction "SHD1_10") (pintype "passive"))
      (node (ref "J8") (pin "11") (pinfunction "SHD2_11") (pintype "passive"))
      (node (ref "R53") (pin "1") (pinfunction "1_1") (pintype "passive"))
    )
    (net (code "59") (name "Net-(J8-VBUS)") (class "Default")
      (node (ref "C9") (pin "1") (pinfunction "1_1") (pintype "passive"))
      (node (ref "J8") (pin "1") (pinfunction "VBUS_1") (pintype "passive"))
      (node (ref "L5") (pin "2") (pinfunction "2_2") (pintype "passive"))
    )
    (net (code "60") (name "Net-(J10-SHD1)") (class "Default")
      (node (ref "C49") (pin "1") (pinfunction "1_1") (pintype "passive"))
      (node (ref "C54") (pin "1") (pinfunction "1_1") (pintype "passive"))
      (node (ref "J10") (pin "10") (pinfunction "SHD1_10") (pintype "passive"))
      (node (ref "J10") (pin "11") (pinfunction "SHD2_11") (pintype "passive"))
      (node (ref "R43") (pin "1") (pinfunction "1_1") (pintype "passive"))
    )
    (net (code "61") (name "Net-(J10-VBUS)") (class "Default")
      (node (ref "C7") (pin "1") (pinfunction "1_1") (pintype "passive"))
      (node (ref "J10") (pin "1") (pinfunction "VBUS_1") (pintype "passive"))
      (node (ref "L4") (pin "2") (pinfunction "2_2") (pintype "passive"))
    )
    (net (code "62") (name "Net-(J11-SHD1)") (class "Default")
      (node (ref "C23") (pin "1") (pinfunction "1_1") (pintype "passive"))
      (node (ref "C32") (pin "1") (pinfunction "1_1") (pintype "passive"))
      (node (ref "J11") (pin "10") (pinfunction "SHD1_10") (pintype "passive"))
      (node (ref "J11") (pin "11") (pinfunction "SHD2_11") (pintype "passive"))
      (node (ref "R42") (pin "1") (pinfunction "1_1") (pintype "passive"))
    )
    (net (code "63") (name "Net-(J11-VBUS)") (class "Default")
      (node (ref "C52") (pin "2") (pinfunction "2_2") (pintype "passive"))
      (node (ref "J11") (pin "1") (pinfunction "VBUS_1") (pintype "passive"))
      (node (ref "L3") (pin "2") (pinfunction "2_2") (pintype "passive"))
    )
    (net (code "64") (name "Net-(J16-SHD1)") (class "Default")
      (node (ref "C14") (pin "1") (pinfunction "1_1") (pintype "passive"))
      (node (ref "C15") (pin "1") (pinfunction "1_1") (pintype "passive"))
      (node (ref "J16") (pin "10") (pinfunction "SHD1_10") (pintype "passive"))
      (node (ref "J16") (pin "11") (pinfunction "SHD2_11") (pintype "passive"))
      (node (ref "R29") (pin "1") (pinfunction "1_1") (pintype "passive"))
    )
    (net (code "65") (name "Net-(J16-VBUS)") (class "Default")
      (node (ref "C11") (pin "1") (pinfunction "1_1") (pintype "passive"))
      (node (ref "J16") (pin "1") (pinfunction "VBUS_1") (pintype "passive"))
      (node (ref "L2") (pin "2") (pinfunction "2_2") (pintype "passive"))
    )
    (net (code "66") (name "Net-(J17-Pad2)") (class "Default")
      (node (ref "J17") (pin "2") (pinfunction "2_2") (pintype "passive"))
      (node (ref "R30") (pin "2") (pinfunction "2_2") (pintype "passive"))
    )
    (net (code "67") (name "Net-(J18-Pad2)") (class "Default")
      (node (ref "J18") (pin "2") (pinfunction "2_2") (pintype "passive"))
      (node (ref "R31") (pin "2") (pinfunction "2_2") (pintype "passive"))
    )
    (net (code "68") (name "Net-(SUSP-CATHODE)") (class "Default")
      (node (ref "R2") (pin "1") (pinfunction "1_1") (pintype "passive"))
      (node (ref "SUSP") (pin "2") (pinfunction "CATHODE_2") (pintype "passive"))
    )
    (net (code "69") (name "Net-(U1A-VBUS_DS)") (class "Default")
      (node (ref "DPR2") (pin "2") (pinfunction "2_2") (pintype "passive"))
      (node (ref "U1") (pin "23") (pinfunction "VBUS_DS_23") (pintype "passive"))
    )
    (net (code "70") (name "Net-(U1A-VBUS_US)") (class "Default")
      (node (ref "R44") (pin "1") (pinfunction "1_1") (pintype "passive"))
      (node (ref "R45") (pin "2") (pinfunction "2_2") (pintype "passive"))
      (node (ref "U1") (pin "22") (pinfunction "VBUS_US_22") (pintype "passive"))
    )
    (net (code "71") (name "Net-(U2-A0)") (class "Default")
      (node (ref "R55") (pin "2") (pinfunction "2_2") (pintype "passive"))
      (node (ref "U2") (pin "1") (pinfunction "A0_1") (pintype "passive"))
    )
    (net (code "72") (name "V3p3") (class "Default")
      (node (ref "C6") (pin "2") (pinfunction "2_2") (pintype "passive"))
      (node (ref "J17") (pin "1") (pinfunction "1_1") (pintype "passive"))
      (node (ref "J18") (pin "1") (pinfunction "1_1") (pintype "passive"))
      (node (ref "J9") (pin "1") (pinfunction "1_1") (pintype "passive"))
      (node (ref "R3") (pin "1") (pinfunction "1_1") (pintype "passive"))
      (node (ref "R5") (pin "2") (pinfunction "2_2") (pintype "passive"))
      (node (ref "R51") (pin "2") (pinfunction "2_2") (pintype "passive"))
      (node (ref "R52") (pin "2") (pinfunction "2_2") (pintype "passive"))
      (node (ref "R55") (pin "1") (pinfunction "1_1") (pintype "passive"))
      (node (ref "R6") (pin "1") (pinfunction "1_1") (pintype "passive"))
      (node (ref "U2") (pin "8") (pinfunction "VCC_8") (pintype "passive"))
    )
    (net (code "73") (name "VBUS_DS1") (class "Default")
      (node (ref "L2") (pin "1") (pinfunction "1_1") (pintype "passive"))
    )
    (net (code "74") (name "VBUS_DS2") (class "Default")
      (node (ref "L4") (pin "1") (pinfunction "1_1") (pintype "passive"))
    )
    (net (code "75") (name "VBUS_DS3") (class "Default")
      (node (ref "L1") (pin "1") (pinfunction "1_1") (pintype "passive"))
    )
    (net (code "76") (name "VBUS_DS4") (class "Default")
      (node (ref "L5") (pin "1") (pinfunction "1_1") (pintype "passive"))
    )
    (net (code "77") (name "VBUS_IN") (class "Default")
      (node (ref "J12") (pin "1") (pinfunction "1_1") (pintype "passive"))
      (node (ref "L3") (pin "1") (pinfunction "1_1") (pintype "passive"))
      (node (ref "TP16") (pin "1") (pinfunction "TP_1") (pintype "passive"))
    )
    (net (code "78") (name "VBUS_PROTECT") (class "Default")
      (node (ref "DPR1") (pin "1") (pinfunction "1_1") (pintype "passive"))
    )
    (net (code "79") (name "VCC_5V") (class "Default")
      (node (ref "DPR1") (pin "3") (pinfunction "3_3") (pintype "passive"))
      (node (ref "DPR2") (pin "1") (pinfunction "1_1") (pintype "passive"))
      (node (ref "J12") (pin "2") (pinfunction "2_2") (pintype "passive"))
    )
  )
)
